# Blinker_Circuit.net
KiCad netlist of a schematic drawn in Altium Designer
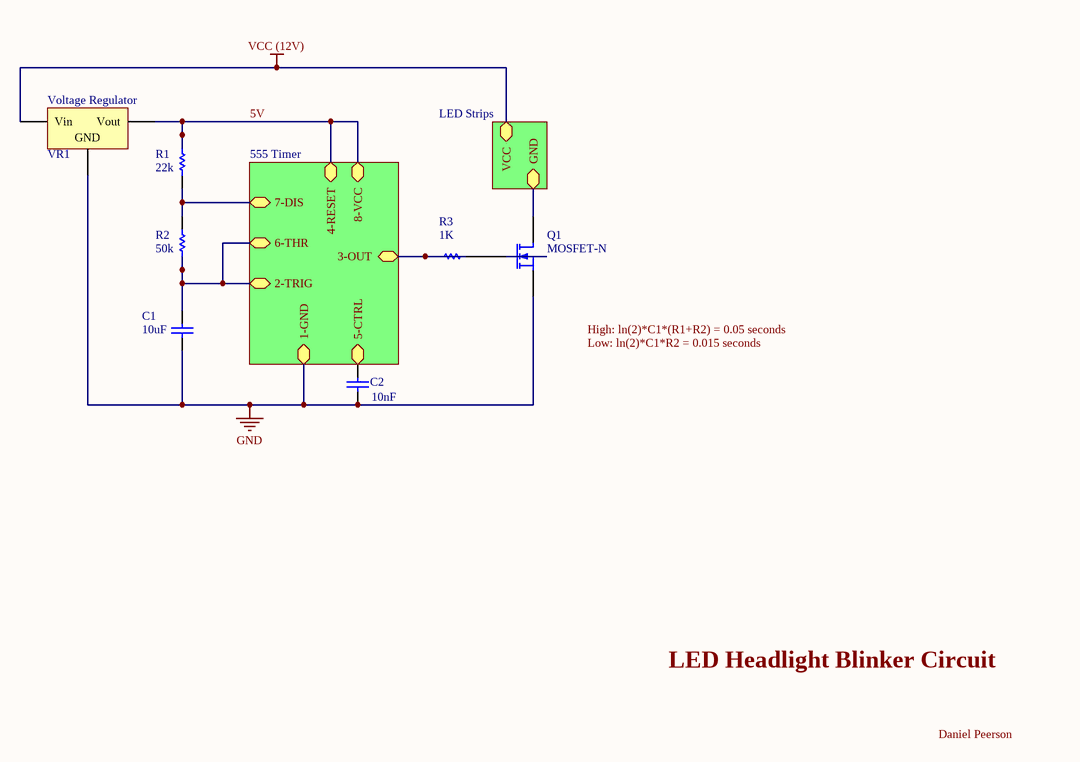
[diagram p0: Blinker_Circuit.SchDoc]

(export (version "E")
  (design (tool "Eeschema 10.0.6"))
  (components
    (comp (ref "C1")
      (value "10uF")
      (footprint "RAD-0.3")
      (description "Capacitor")
      (fields (field (name "Comment") "Cap") (field (name "PUBLISHER") "Altium Limited"))
      (libsource (lib "Miscellaneous Devices") (part "Cap"))
    )
    (comp (ref "C2")
      (value "10nF")
      (footprint "RAD-0.3")
      (description "Capacitor")
      (fields (field (name "Comment") "Cap") (field (name "PUBLISHER") "Altium Limited"))
      (libsource (lib "Miscellaneous Devices") (part "Cap"))
    )
    (comp (ref "Q1")
      (value "MOSFET-N")
      (footprint "E3")
      (description "N-Channel MOSFET")
      (fields (field (name "PUBLISHER") "Altium Limited"))
      (libsource (lib "Miscellaneous Devices") (part "MOSFET-N"))
    )
    (comp (ref "R1")
      (value "22k")
      (footprint "AXIAL-0.3")
      (description "Resistor")
      (fields (field (name "Comment") "Res1") (field (name "PUBLISHER") "Altium Limited"))
      (libsource (lib "Miscellaneous Devices") (part "Res1"))
    )
    (comp (ref "R2")
      (value "50k")
      (footprint "AXIAL-0.3")
      (description "Resistor")
      (fields (field (name "Comment") "Res1") (field (name "PUBLISHER") "Altium Limited"))
      (libsource (lib "Miscellaneous Devices") (part "Res1"))
    )
    (comp (ref "R3")
      (value "1K")
      (footprint "AXIAL-0.3")
      (description "Resistor")
      (fields (field (name "Comment") "Res1") (field (name "PUBLISHER") "Altium Limited"))
      (libsource (lib "Miscellaneous Devices") (part "Res1"))
    )
    (comp (ref "VR1")
      (value "Voltage Regulator")
      (footprint "D2PAK_N")
      (fields (field (name "PUBLISHER") "Altium Limited"))
      (libsource (lib "Miscellaneous Devices") (part "Volt Reg"))
    )
  )
  (nets
    (net (code "1") (name "/2-TRIG") (class "Default")
      (node (ref "C1") (pin "2") (pinfunction "2_2") (pintype "passive"))
      (node (ref "R2") (pin "1") (pinfunction "1_1") (pintype "passive"))
    )
    (net (code "2") (name "/3-OUT") (class "Default")
      (node (ref "R3") (pin "1") (pinfunction "1_1") (pintype "passive"))
    )
    (net (code "3") (name "/5-CTRL") (class "Default")
      (node (ref "C2") (pin "2") (pinfunction "2_2") (pintype "passive"))
    )
    (net (code "4") (name "/5V") (class "Default")
      (node (ref "R1") (pin "2") (pinfunction "2_2") (pintype "passive"))
      (node (ref "VR1") (pin "3") (pinfunction "Vout_3") (pintype "passive"))
    )
    (net (code "5") (name "/7-DIS") (class "Default")
      (node (ref "R1") (pin "1") (pinfunction "1_1") (pintype "passive"))
      (node (ref "R2") (pin "2") (pinfunction "2_2") (pintype "passive"))
    )
    (net (code "7") (name "/GND") (class "Default")
      (node (ref "Q1") (pin "1") (pinfunction "D_1") (pintype "passive"))
    )
    (net (code "11") (name "GND") (class "Default")
      (node (ref "C1") (pin "1") (pinfunction "1_1") (pintype "passive"))
      (node (ref "C2") (pin "1") (pinfunction "1_1") (pintype "passive"))
      (node (ref "Q1") (pin "3") (pinfunction "S_3") (pintype "passive"))
      (node (ref "VR1") (pin "2") (pinfunction "GND_2") (pintype "passive"))
    )
    (net (code "12") (name "Net-(Q1-G)") (class "Default")
      (node (ref "Q1") (pin "2") (pinfunction "G_2") (pintype "passive"))
      (node (ref "R3") (pin "2") (pinfunction "2_2") (pintype "passive"))
    )
    (net (code "13") (name "VCC (12V)") (class "Default")
      (node (ref "VR1") (pin "1") (pinfunction "Vin_1") (pintype "passive"))
    )
  )
)
